# Adafruit_Pro_Trinket_3v3.net
KiCad netlist of a schematic drawn in EAGLE
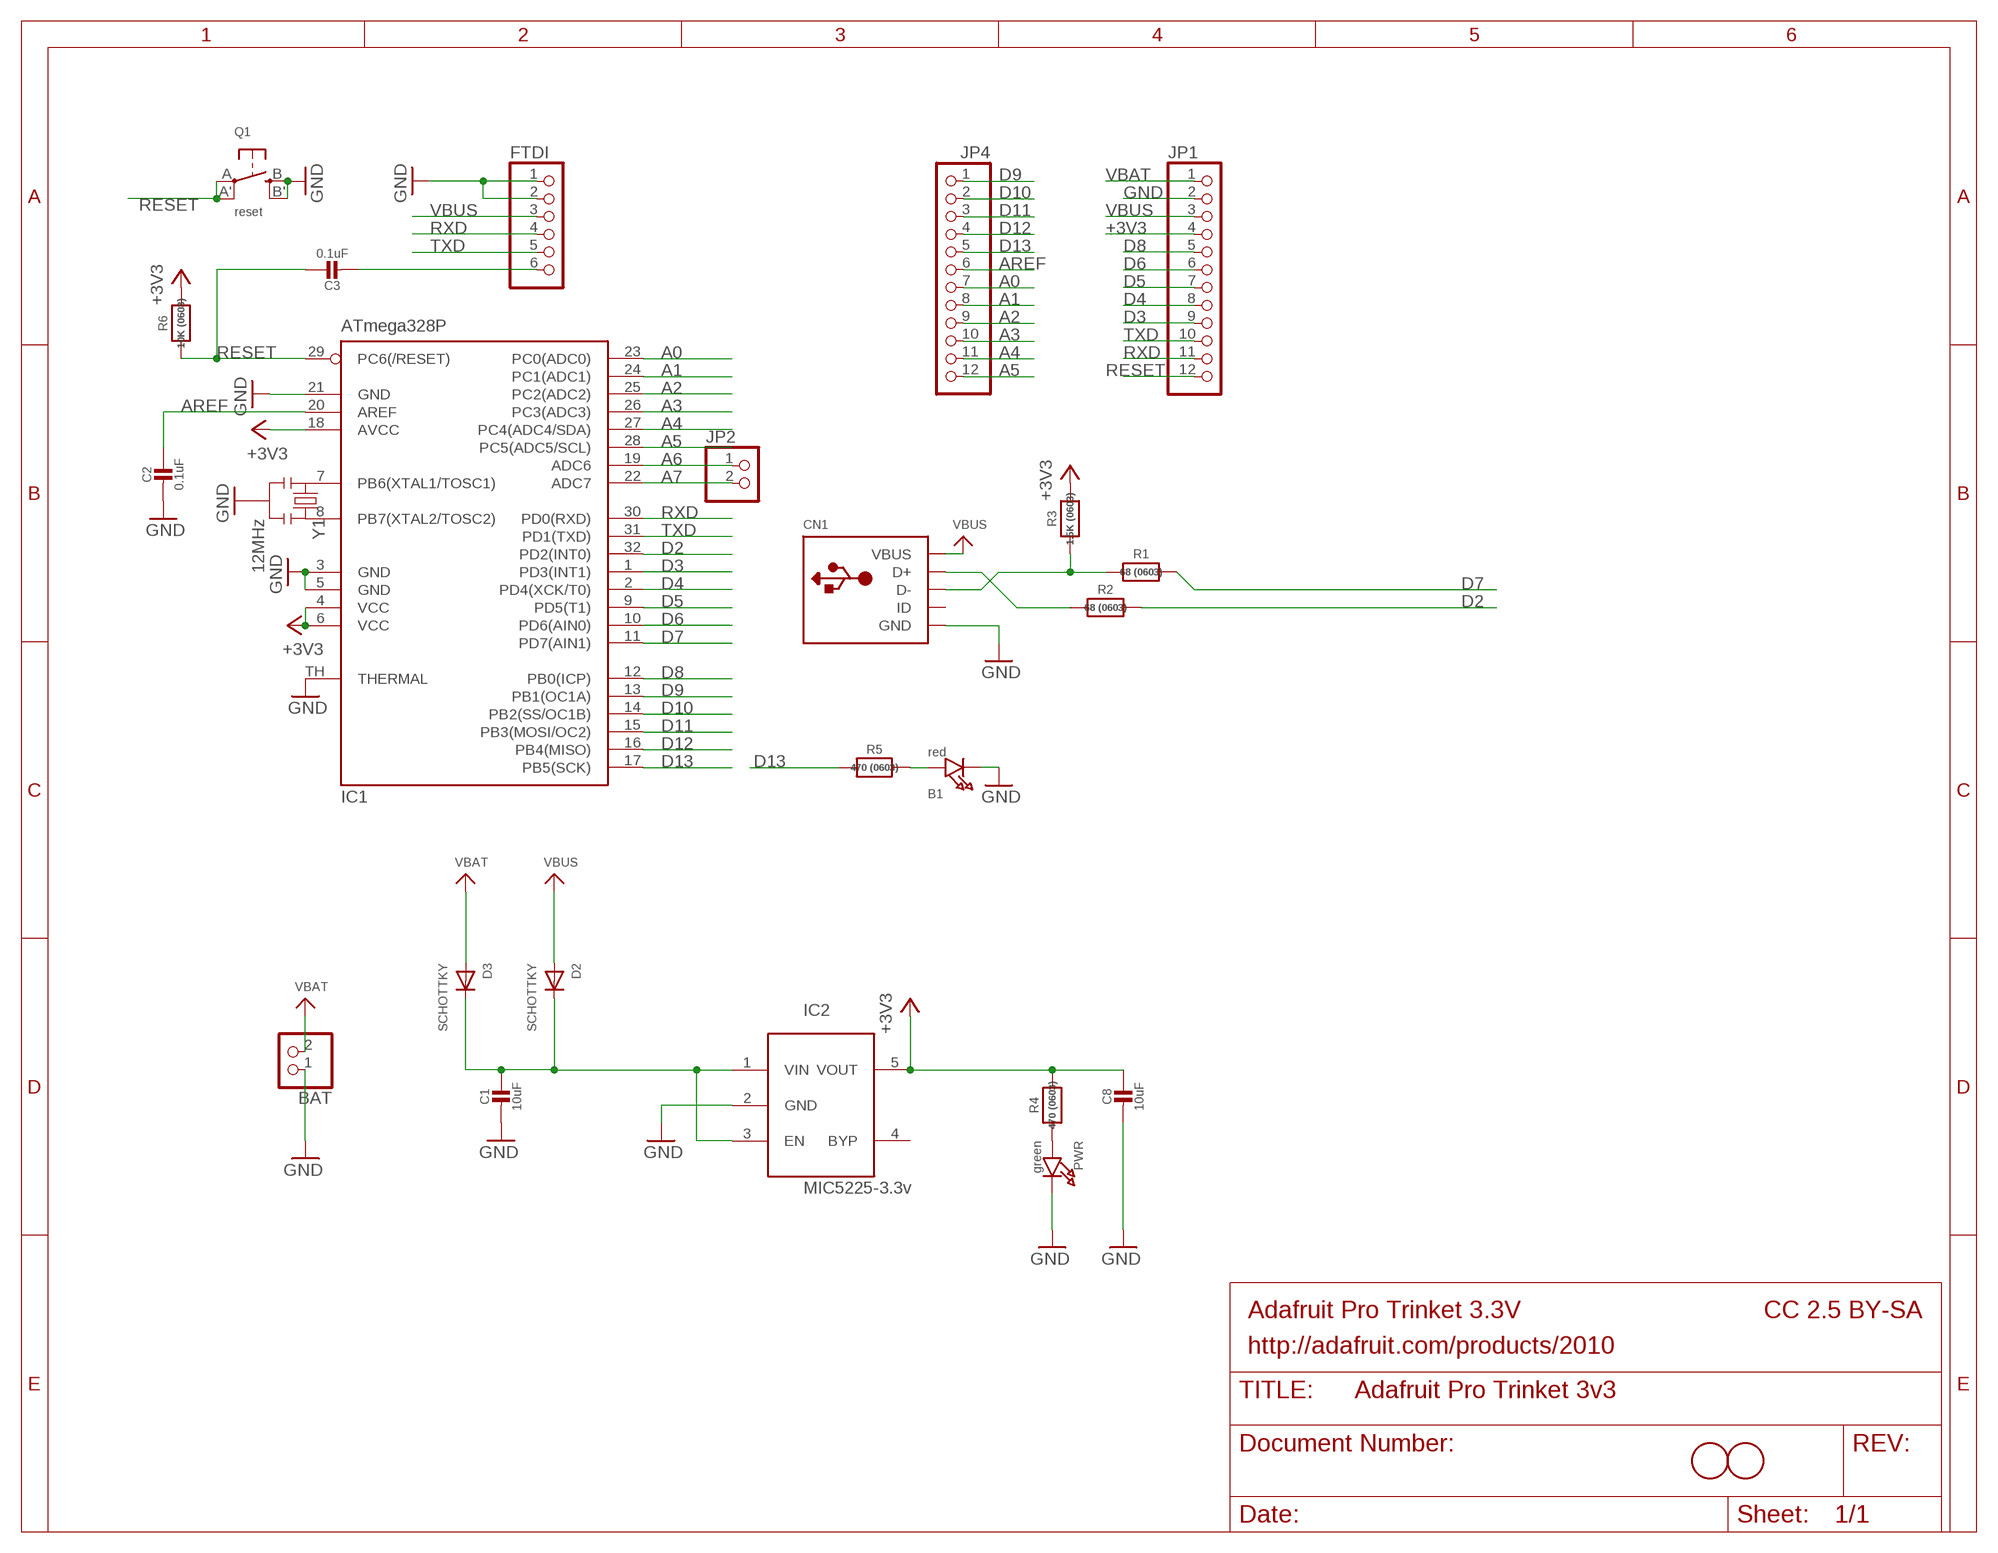
[diagram p0: schematic, sheet 1]

(export (version "E")
  (design (tool "Eeschema 10.0.6"))
  (components
    (comp (ref "B1")
      (value "red")
      (footprint "eagle-import:CHIPLED_0805_NOOUTLINE")
      (libsource (lib "eagle-import") (part "LED0805_NOOUTLINE"))
    )
    (comp (ref "BAT")
      (value "CON_JST_PH_2PIN")
      (footprint "eagle-import:JSTPH2")
      (libsource (lib "eagle-import") (part "CON_JST_PH_2PIN"))
    )
    (comp (ref "C1")
      (value "10uF")
      (footprint "eagle-import:0805-NO")
      (libsource (lib "eagle-import") (part "CAP_CERAMIC0805-NOOUTLINE"))
    )
    (comp (ref "C2")
      (value "0.1uF")
      (footprint "eagle-import:_0805MP")
      (libsource (lib "eagle-import") (part "CAP_CERAMIC_0805MP"))
    )
    (comp (ref "C3")
      (value "0.1uF")
      (footprint "eagle-import:0805-NO")
      (libsource (lib "eagle-import") (part "CAP_CERAMIC0805-NOOUTLINE"))
    )
    (comp (ref "C8")
      (value "10uF")
      (footprint "eagle-import:0805-NO")
      (libsource (lib "eagle-import") (part "CAP_CERAMIC0805-NOOUTLINE"))
    )
    (comp (ref "CN1")
      (value "USBMICRO_20329")
      (footprint "eagle-import:4UCONN_20329")
      (libsource (lib "eagle-import") (part "USBMICRO_20329"))
    )
    (comp (ref "D2")
      (value "SCHOTTKY")
      (footprint "eagle-import:SOD-123FL")
      (libsource (lib "eagle-import") (part "DIODE_SOD-123FL"))
    )
    (comp (ref "D3")
      (value "SCHOTTKY")
      (footprint "eagle-import:SOD-123FL")
      (libsource (lib "eagle-import") (part "DIODE_SOD-123FL"))
    )
    (comp (ref "FTDI")
      (value "PINHD-1X6CB")
      (footprint "eagle-import:1X06-CLEANBIG")
      (libsource (lib "eagle-import") (part "PINHD-1X6CB"))
    )
    (comp (ref "IC1")
      (value "ATmega328P")
      (footprint "eagle-import:MLF32-TH")
      (fields (field (name "MPN") "ATMEGA88PA-MU"))
      (libsource (lib "eagle-import") (part "MEGA8-MI"))
    )
    (comp (ref "IC2")
      (value "MIC5225-3.3v")
      (footprint "eagle-import:SOT23-5L")
      (libsource (lib "eagle-import") (part "LP298XS"))
    )
    (comp (ref "JP1")
      (value "PINHD-1X12-CB")
      (footprint "eagle-import:1X12-CB")
      (libsource (lib "eagle-import") (part "PINHD-1X12-CB"))
    )
    (comp (ref "JP2")
      (value "HEADER-1X2ROUND")
      (footprint "eagle-import:1X02_ROUND")
      (libsource (lib "eagle-import") (part "HEADER-1X2ROUND"))
    )
    (comp (ref "JP4")
      (value "PINHD-1X12-CB")
      (footprint "eagle-import:1X12-CB")
      (libsource (lib "eagle-import") (part "PINHD-1X12-CB"))
    )
    (comp (ref "PWR")
      (value "green")
      (footprint "eagle-import:CHIPLED_0805_NOOUTLINE")
      (libsource (lib "eagle-import") (part "LED0805_NOOUTLINE"))
    )
    (comp (ref "Q1")
      (value "reset")
      (footprint "eagle-import:BTN_KMR2_4.6X2.8")
      (libsource (lib "eagle-import") (part "SWITCH_TACT_SMT4.6X2.8"))
    )
    (comp (ref "R1")
      (value "68 (0603)")
      (footprint "eagle-import:0603-NO")
      (libsource (lib "eagle-import") (part "RESISTOR_0603_NOOUT"))
    )
    (comp (ref "R2")
      (value "68 (0603)")
      (footprint "eagle-import:0603-NO")
      (libsource (lib "eagle-import") (part "RESISTOR_0603_NOOUT"))
    )
    (comp (ref "R3")
      (value "1.5K (0603)")
      (footprint "eagle-import:0603-NO")
      (libsource (lib "eagle-import") (part "RESISTOR_0603_NOOUT"))
    )
    (comp (ref "R4")
      (value "470 (0603)")
      (footprint "eagle-import:0603-NO")
      (libsource (lib "eagle-import") (part "RESISTOR_0603_NOOUT"))
    )
    (comp (ref "R5")
      (value "470 (0603)")
      (footprint "eagle-import:0603-NO")
      (libsource (lib "eagle-import") (part "RESISTOR_0603_NOOUT"))
    )
    (comp (ref "R6")
      (value "10K (0603)")
      (footprint "eagle-import:0805-NO")
      (libsource (lib "eagle-import") (part "RESISTOR0805_NOOUTLINE"))
    )
    (comp (ref "U$1")
      (value "FIDUCIAL")
      (footprint "eagle-import:FIDUCIAL_1MM")
      (libsource (lib "eagle-import") (part "FIDUCIAL"))
    )
    (comp (ref "U$6")
      (value "FIDUCIAL")
      (footprint "eagle-import:FIDUCIAL_1MM")
      (libsource (lib "eagle-import") (part "FIDUCIAL"))
    )
    (comp (ref "Y1")
      (value "12MHz")
      (footprint "eagle-import:RESONATOR-SMD")
      (libsource (lib "eagle-import") (part "RESONATORSMD"))
    )
  )
  (nets
    (net (code "1") (name "+3V3") (class "Default")
      (node (ref "C8") (pin "1") (pinfunction "1_1") (pintype "passive"))
      (node (ref "IC1") (pin "18") (pinfunction "AVCC_18") (pintype "power_in"))
      (node (ref "IC1") (pin "4") (pinfunction "VCC_4") (pintype "power_in"))
      (node (ref "IC1") (pin "6") (pinfunction "VCC_6") (pintype "power_in"))
      (node (ref "IC2") (pin "5") (pinfunction "VOUT_5") (pintype "bidirectional"))
      (node (ref "JP1") (pin "4") (pinfunction "4_4") (pintype "passive"))
      (node (ref "R3") (pin "2") (pinfunction "2_2") (pintype "passive"))
      (node (ref "R4") (pin "2") (pinfunction "2_2") (pintype "passive"))
      (node (ref "R6") (pin "2") (pinfunction "2_2") (pintype "passive"))
    )
    (net (code "2") (name "/A0") (class "Default")
      (node (ref "IC1") (pin "23") (pinfunction "PC0(ADC0)_23") (pintype "bidirectional"))
      (node (ref "JP4") (pin "7") (pinfunction "7_7") (pintype "passive"))
    )
    (net (code "3") (name "/A1") (class "Default")
      (node (ref "IC1") (pin "24") (pinfunction "PC1(ADC1)_24") (pintype "bidirectional"))
      (node (ref "JP4") (pin "8") (pinfunction "8_8") (pintype "passive"))
    )
    (net (code "4") (name "/A2") (class "Default")
      (node (ref "IC1") (pin "25") (pinfunction "PC2(ADC2)_25") (pintype "bidirectional"))
      (node (ref "JP4") (pin "9") (pinfunction "9_9") (pintype "passive"))
    )
    (net (code "5") (name "/A3") (class "Default")
      (node (ref "IC1") (pin "26") (pinfunction "PC3(ADC3)_26") (pintype "bidirectional"))
      (node (ref "JP4") (pin "10") (pinfunction "10_10") (pintype "passive"))
    )
    (net (code "6") (name "/A4") (class "Default")
      (node (ref "IC1") (pin "27") (pinfunction "PC4(ADC4/SDA)_27") (pintype "bidirectional"))
      (node (ref "JP4") (pin "11") (pinfunction "11_11") (pintype "passive"))
    )
    (net (code "7") (name "/A5") (class "Default")
      (node (ref "IC1") (pin "28") (pinfunction "PC5(ADC5/SCL)_28") (pintype "bidirectional"))
      (node (ref "JP4") (pin "12") (pinfunction "12_12") (pintype "passive"))
    )
    (net (code "8") (name "/A6") (class "Default")
      (node (ref "IC1") (pin "19") (pinfunction "ADC6_19") (pintype "bidirectional"))
      (node (ref "JP2") (pin "1") (pinfunction "1_1") (pintype "passive"))
    )
    (net (code "9") (name "/A7") (class "Default")
      (node (ref "IC1") (pin "22") (pinfunction "ADC7_22") (pintype "bidirectional"))
      (node (ref "JP2") (pin "2") (pinfunction "2_2") (pintype "passive"))
    )
    (net (code "10") (name "/AREF") (class "Default")
      (node (ref "C2") (pin "1") (pinfunction "1_1") (pintype "passive"))
      (node (ref "IC1") (pin "20") (pinfunction "AREF_20") (pintype "passive"))
      (node (ref "JP4") (pin "6") (pinfunction "6_6") (pintype "passive"))
    )
    (net (code "11") (name "/D2") (class "Default")
      (node (ref "IC1") (pin "32") (pinfunction "PD2(INT0)_32") (pintype "bidirectional"))
      (node (ref "R2") (pin "2") (pinfunction "2_2") (pintype "passive"))
    )
    (net (code "12") (name "/D3") (class "Default")
      (node (ref "IC1") (pin "1") (pinfunction "PD3(INT1)_1") (pintype "bidirectional"))
      (node (ref "JP1") (pin "9") (pinfunction "9_9") (pintype "passive"))
    )
    (net (code "13") (name "/D4") (class "Default")
      (node (ref "IC1") (pin "2") (pinfunction "PD4(XCK/T0)_2") (pintype "bidirectional"))
      (node (ref "JP1") (pin "8") (pinfunction "8_8") (pintype "passive"))
    )
    (net (code "14") (name "/D5") (class "Default")
      (node (ref "IC1") (pin "9") (pinfunction "PD5(T1)_9") (pintype "bidirectional"))
      (node (ref "JP1") (pin "7") (pinfunction "7_7") (pintype "passive"))
    )
    (net (code "15") (name "/D6") (class "Default")
      (node (ref "IC1") (pin "10") (pinfunction "PD6(AIN0)_10") (pintype "bidirectional"))
      (node (ref "JP1") (pin "6") (pinfunction "6_6") (pintype "passive"))
    )
    (net (code "16") (name "/D7") (class "Default")
      (node (ref "IC1") (pin "11") (pinfunction "PD7(AIN1)_11") (pintype "bidirectional"))
      (node (ref "R1") (pin "2") (pinfunction "2_2") (pintype "passive"))
    )
    (net (code "17") (name "/D8") (class "Default")
      (node (ref "IC1") (pin "12") (pinfunction "PB0(ICP)_12") (pintype "bidirectional"))
      (node (ref "JP1") (pin "5") (pinfunction "5_5") (pintype "passive"))
    )
    (net (code "18") (name "/D9") (class "Default")
      (node (ref "IC1") (pin "13") (pinfunction "PB1(OC1A)_13") (pintype "bidirectional"))
      (node (ref "JP4") (pin "1") (pinfunction "1_1") (pintype "passive"))
    )
    (net (code "19") (name "/D10") (class "Default")
      (node (ref "IC1") (pin "14") (pinfunction "PB2(SS/OC1B)_14") (pintype "bidirectional"))
      (node (ref "JP4") (pin "2") (pinfunction "2_2") (pintype "passive"))
    )
    (net (code "20") (name "/D11") (class "Default")
      (node (ref "IC1") (pin "15") (pinfunction "PB3(MOSI/OC2)_15") (pintype "bidirectional"))
      (node (ref "JP4") (pin "3") (pinfunction "3_3") (pintype "passive"))
    )
    (net (code "21") (name "/D12") (class "Default")
      (node (ref "IC1") (pin "16") (pinfunction "PB4(MISO)_16") (pintype "bidirectional"))
      (node (ref "JP4") (pin "4") (pinfunction "4_4") (pintype "passive"))
    )
    (net (code "22") (name "/D13") (class "Default")
      (node (ref "IC1") (pin "17") (pinfunction "PB5(SCK)_17") (pintype "bidirectional"))
      (node (ref "JP4") (pin "5") (pinfunction "5_5") (pintype "passive"))
      (node (ref "R5") (pin "2") (pinfunction "2_2") (pintype "passive"))
    )
    (net (code "23") (name "/RESET") (class "Default")
      (node (ref "C3") (pin "1") (pinfunction "1_1") (pintype "passive"))
      (node (ref "IC1") (pin "29") (pinfunction "PC6(/RESET)_29") (pintype "bidirectional"))
      (node (ref "JP1") (pin "12") (pinfunction "12_12") (pintype "passive"))
      (node (ref "Q1") (pin "A") (pinfunction "P_A") (pintype "passive"))
      (node (ref "Q1") (pin "A'") (pinfunction "P1_A'") (pintype "passive"))
      (node (ref "R6") (pin "1") (pinfunction "1_1") (pintype "passive"))
    )
    (net (code "24") (name "/RXD") (class "Default")
      (node (ref "FTDI") (pin "4") (pinfunction "4_4") (pintype "passive"))
      (node (ref "IC1") (pin "30") (pinfunction "PD0(RXD)_30") (pintype "bidirectional"))
      (node (ref "JP1") (pin "11") (pinfunction "11_11") (pintype "passive"))
    )
    (net (code "25") (name "/TXD") (class "Default")
      (node (ref "FTDI") (pin "5") (pinfunction "5_5") (pintype "passive"))
      (node (ref "IC1") (pin "31") (pinfunction "PD1(TXD)_31") (pintype "bidirectional"))
      (node (ref "JP1") (pin "10") (pinfunction "10_10") (pintype "passive"))
    )
    (net (code "26") (name "GND") (class "Default")
      (node (ref "B1") (pin "C") (pinfunction "C_C") (pintype "passive"))
      (node (ref "BAT") (pin "1") (pinfunction "1_1") (pintype "passive"))
      (node (ref "C1") (pin "2") (pinfunction "2_2") (pintype "passive"))
      (node (ref "C2") (pin "2") (pinfunction "2_2") (pintype "passive"))
      (node (ref "C8") (pin "2") (pinfunction "2_2") (pintype "passive"))
      (node (ref "CN1") (pin "BASE@1") (pinfunction "GND_BASE@1") (pintype "power_in"))
      (node (ref "CN1") (pin "BASE@2") (pinfunction "GND_BASE@2") (pintype "power_in"))
      (node (ref "CN1") (pin "GND") (pinfunction "GND_GND") (pintype "power_in"))
      (node (ref "CN1") (pin "SPRT@1") (pinfunction "GND_SPRT@1") (pintype "power_in"))
      (node (ref "CN1") (pin "SPRT@2") (pinfunction "GND_SPRT@2") (pintype "power_in"))
      (node (ref "CN1") (pin "SPRT@3") (pinfunction "GND_SPRT@3") (pintype "power_in"))
      (node (ref "CN1") (pin "SPRT@4") (pinfunction "GND_SPRT@4") (pintype "power_in"))
      (node (ref "FTDI") (pin "1") (pinfunction "1_1") (pintype "passive"))
      (node (ref "FTDI") (pin "2") (pinfunction "2_2") (pintype "passive"))
      (node (ref "IC1") (pin "21") (pinfunction "GND_21") (pintype "power_in"))
      (node (ref "IC1") (pin "3") (pinfunction "GND_3") (pintype "power_in"))
      (node (ref "IC1") (pin "5") (pinfunction "GND_5") (pintype "power_in"))
      (node (ref "IC1") (pin "TH") (pinfunction "THERMAL_TH") (pintype "passive"))
      (node (ref "IC2") (pin "2") (pinfunction "GND_2") (pintype "bidirectional"))
      (node (ref "JP1") (pin "2") (pinfunction "2_2") (pintype "passive"))
      (node (ref "PWR") (pin "C") (pinfunction "C_C") (pintype "passive"))
      (node (ref "Q1") (pin "B") (pinfunction "S_B") (pintype "passive"))
      (node (ref "Q1") (pin "B'") (pinfunction "S1_B'") (pintype "passive"))
      (node (ref "Y1") (pin "2") (pinfunction "2_2") (pintype "passive"))
    )
    (net (code "27") (name "Net-(B1-PadA)") (class "Default")
      (node (ref "B1") (pin "A") (pinfunction "A_A") (pintype "passive"))
      (node (ref "R5") (pin "1") (pinfunction "1_1") (pintype "passive"))
    )
    (net (code "28") (name "Net-(C3-Pad2)") (class "Default")
      (node (ref "C3") (pin "2") (pinfunction "2_2") (pintype "passive"))
      (node (ref "FTDI") (pin "6") (pinfunction "6_6") (pintype "passive"))
    )
    (net (code "29") (name "Net-(CN1-PadD+)") (class "Default")
      (node (ref "CN1") (pin "D+") (pinfunction "D+_D+") (pintype "bidirectional"))
      (node (ref "R2") (pin "1") (pinfunction "1_1") (pintype "passive"))
    )
    (net (code "30") (name "Net-(CN1-PadD-)") (class "Default")
      (node (ref "CN1") (pin "D-") (pinfunction "D-_D-") (pintype "bidirectional"))
      (node (ref "R1") (pin "1") (pinfunction "1_1") (pintype "passive"))
      (node (ref "R3") (pin "1") (pinfunction "1_1") (pintype "passive"))
    )
    (net (code "31") (name "Net-(IC1-PB6(XTAL1{slash}TOSC1))") (class "Default")
      (node (ref "IC1") (pin "7") (pinfunction "PB6(XTAL1/TOSC1)_7") (pintype "bidirectional"))
      (node (ref "Y1") (pin "1") (pinfunction "1_1") (pintype "passive"))
    )
    (net (code "32") (name "Net-(IC1-PB7(XTAL2{slash}TOSC2))") (class "Default")
      (node (ref "IC1") (pin "8") (pinfunction "PB7(XTAL2/TOSC2)_8") (pintype "bidirectional"))
      (node (ref "Y1") (pin "3") (pinfunction "3_3") (pintype "passive"))
    )
    (net (code "33") (name "Net-(IC2-EN)") (class "Default")
      (node (ref "C1") (pin "1") (pinfunction "1_1") (pintype "passive"))
      (node (ref "D2") (pin "C") (pinfunction "C_C") (pintype "passive"))
      (node (ref "D3") (pin "C") (pinfunction "C_C") (pintype "passive"))
      (node (ref "IC2") (pin "1") (pinfunction "VIN_1") (pintype "bidirectional"))
      (node (ref "IC2") (pin "3") (pinfunction "EN_3") (pintype "bidirectional"))
    )
    (net (code "34") (name "Net-(PWR-PadA)") (class "Default")
      (node (ref "PWR") (pin "A") (pinfunction "A_A") (pintype "passive"))
      (node (ref "R4") (pin "1") (pinfunction "1_1") (pintype "passive"))
    )
    (net (code "35") (name "VBAT") (class "Default")
      (node (ref "BAT") (pin "2") (pinfunction "2_2") (pintype "passive"))
      (node (ref "D3") (pin "A") (pinfunction "A_A") (pintype "passive"))
      (node (ref "JP1") (pin "1") (pinfunction "1_1") (pintype "passive"))
    )
    (net (code "36") (name "VBUS") (class "Default")
      (node (ref "CN1") (pin "VBUS") (pinfunction "VBUS_VBUS") (pintype "power_in"))
      (node (ref "D2") (pin "A") (pinfunction "A_A") (pintype "passive"))
      (node (ref "FTDI") (pin "3") (pinfunction "3_3") (pintype "passive"))
      (node (ref "JP1") (pin "3") (pinfunction "3_3") (pintype "passive"))
    )
    (net (code "37") (name "unconnected-(CN1-PadID)") (class "Default")
      (node (ref "CN1") (pin "ID") (pinfunction "ID_ID") (pintype "bidirectional"))
    )
    (net (code "38") (name "unconnected-(IC2-BYP-Pad4)") (class "Default")
      (node (ref "IC2") (pin "4") (pinfunction "BYP_4") (pintype "bidirectional"))
    )
  )
)
